# STM32.net
KiCad netlist of a schematic drawn in Altium Designer
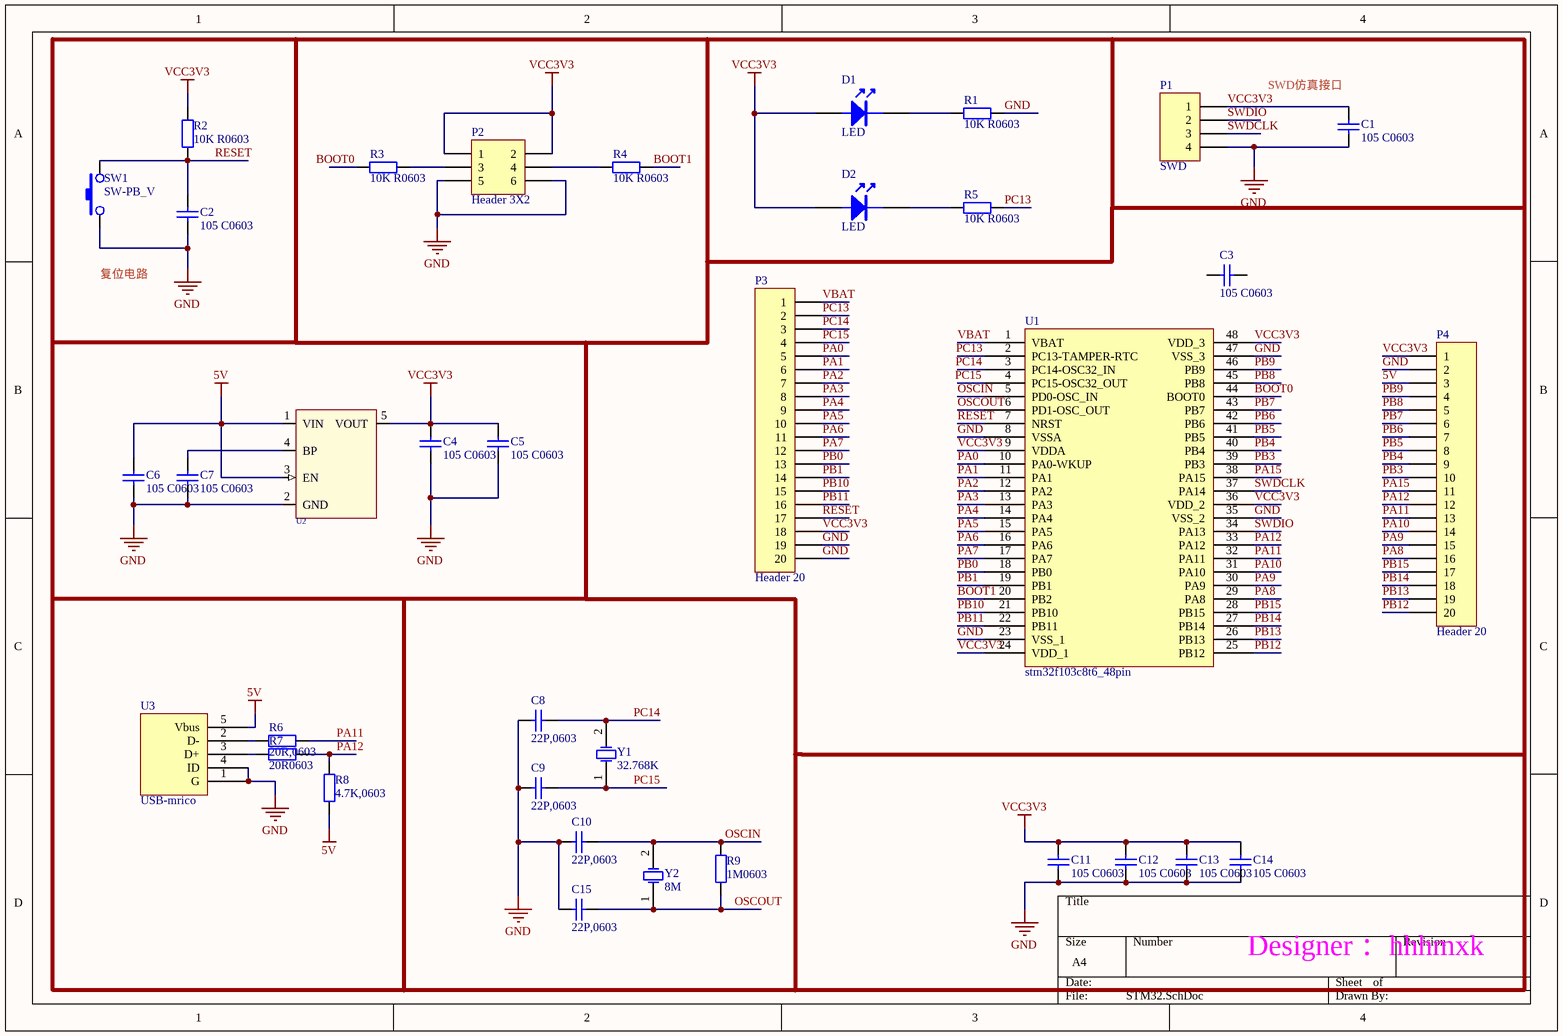
[diagram p0: STM32.SchDoc]

(export (version "E")
  (design (tool "Eeschema 10.0.6"))
  (components
    (comp (ref "C1")
      (value "105 C0603")
      (footprint "C 0603")
      (fields (field (name "PUBLISHER") "Altium Limited"))
      (libsource (lib "stm32原理图库") (part "Cap"))
    )
    (comp (ref "C2")
      (value "105 C0603")
      (footprint "C 0603")
      (fields (field (name "PUBLISHER") "Altium Limited"))
      (libsource (lib "stm32原理图库") (part "Cap"))
    )
    (comp (ref "C3")
      (value "105 C0603")
      (footprint "C 0603")
      (fields (field (name "PUBLISHER") "Altium Limited"))
      (libsource (lib "stm32原理图库") (part "Cap"))
    )
    (comp (ref "C4")
      (value "105 C0603")
      (footprint "C 0603")
      (fields (field (name "PUBLISHER") "Altium Limited"))
      (libsource (lib "stm32原理图库") (part "Cap"))
    )
    (comp (ref "C5")
      (value "105 C0603")
      (footprint "C 0603")
      (fields (field (name "PUBLISHER") "Altium Limited"))
      (libsource (lib "stm32原理图库") (part "Cap"))
    )
    (comp (ref "C6")
      (value "105 C0603")
      (footprint "C 0603")
      (fields (field (name "PUBLISHER") "Altium Limited"))
      (libsource (lib "stm32原理图库") (part "Cap"))
    )
    (comp (ref "C7")
      (value "105 C0603")
      (footprint "C 0603")
      (fields (field (name "PUBLISHER") "Altium Limited"))
      (libsource (lib "stm32原理图库") (part "Cap"))
    )
    (comp (ref "C8")
      (value "22P,0603")
      (footprint "C 0603")
      (description "Capacitor")
      (fields (field (name "PUBLISHER") "Altium Limited"))
      (libsource (lib "STM32F103C8T6") (part "Cap"))
    )
    (comp (ref "C9")
      (value "22P,0603")
      (footprint "C 0603")
      (description "Capacitor")
      (fields (field (name "PUBLISHER") "Altium Limited"))
      (libsource (lib "STM32F103C8T6") (part "Cap"))
    )
    (comp (ref "C10")
      (value "22P,0603")
      (footprint "C 0603")
      (description "Capacitor")
      (fields (field (name "PUBLISHER") "Altium Limited"))
      (libsource (lib "STM32F103C8T6") (part "Cap"))
    )
    (comp (ref "C11")
      (value "105 C0603")
      (footprint "C 0603")
      (fields (field (name "PUBLISHER") "Altium Limited"))
      (libsource (lib "stm32原理图库") (part "Cap"))
    )
    (comp (ref "C12")
      (value "105 C0603")
      (footprint "C 0603")
      (fields (field (name "PUBLISHER") "Altium Limited"))
      (libsource (lib "stm32原理图库") (part "Cap"))
    )
    (comp (ref "C13")
      (value "105 C0603")
      (footprint "C 0603")
      (fields (field (name "PUBLISHER") "Altium Limited"))
      (libsource (lib "stm32原理图库") (part "Cap"))
    )
    (comp (ref "C14")
      (value "105 C0603")
      (footprint "C 0603")
      (fields (field (name "PUBLISHER") "Altium Limited"))
      (libsource (lib "stm32原理图库") (part "Cap"))
    )
    (comp (ref "C15")
      (value "22P,0603")
      (footprint "C 0603")
      (description "Capacitor")
      (fields (field (name "PUBLISHER") "Altium Limited"))
      (libsource (lib "STM32F103C8T6") (part "Cap"))
    )
    (comp (ref "D1") (value "LED") (footprint "LED 0805G") (libsource (lib "stm32原理图库") (part "LED")))
    (comp (ref "D2") (value "LED") (footprint "LED 0805G") (libsource (lib "stm32原理图库") (part "LED")))
    (comp (ref "P1")
      (value "SWD")
      (footprint "HDR-1X4_H")
      (description "Header, 4-Pin")
      (fields (field (name "PUBLISHER") "Altium Limited"))
      (libsource (lib "stm32原理图库") (part "Header 4"))
    )
    (comp (ref "P2")
      (value "Header 3X2")
      (footprint "HDR-3X2")
      (description "Header, 3-Pin, Dual row")
      (fields (field (name "PUBLISHER") "Altium Limited"))
      (libsource (lib "stm32原理图库") (part "Header 3X2"))
    )
    (comp (ref "P3")
      (value "Header 20")
      (footprint "HDR1X20")
      (description "Header, 20-Pin")
      (fields (field (name "PUBLISHER") "Altium Limited"))
      (libsource (lib "stm32原理图库") (part "Header 20"))
    )
    (comp (ref "P4")
      (value "Header 20")
      (footprint "HDR1X20")
      (description "Header, 20-Pin")
      (fields (field (name "PUBLISHER") "Altium Limited"))
      (libsource (lib "") (part "Header 20_1"))
    )
    (comp (ref "R1")
      (value "10K R0603")
      (footprint "R 0603")
      (fields (field (name "PUBLISHER") "Altium Limited"))
      (libsource (lib "stm32原理图库") (part "Res2"))
    )
    (comp (ref "R2")
      (value "10K R0603")
      (footprint "R 0603")
      (fields (field (name "PUBLISHER") "Altium Limited"))
      (libsource (lib "") (part "Res2_1"))
    )
    (comp (ref "R3")
      (value "10K R0603")
      (footprint "R 0603")
      (fields (field (name "PUBLISHER") "Altium Limited"))
      (libsource (lib "stm32原理图库") (part "Res2"))
    )
    (comp (ref "R4")
      (value "10K R0603")
      (footprint "R 0603")
      (fields (field (name "PUBLISHER") "Altium Limited"))
      (libsource (lib "stm32原理图库") (part "Res2"))
    )
    (comp (ref "R5")
      (value "10K R0603")
      (footprint "R 0603")
      (fields (field (name "PUBLISHER") "Altium Limited"))
      (libsource (lib "stm32原理图库") (part "Res2"))
    )
    (comp (ref "R6")
      (value "20R,0603")
      (footprint "R 0603")
      (description "Resistor")
      (fields (field (name "PUBLISHER") "Altium Limited"))
      (libsource (lib "") (part "Res2_1"))
    )
    (comp (ref "R7")
      (value "20R0603")
      (footprint "R 0603")
      (description "Resistor")
      (fields (field (name "PUBLISHER") "Altium Limited"))
      (libsource (lib "") (part "Res2_1"))
    )
    (comp (ref "R8")
      (value "4.7K,0603")
      (footprint "R 0603")
      (description "Resistor")
      (fields (field (name "PUBLISHER") "Altium Limited"))
      (libsource (lib "STM32F103C8T6") (part "Res2"))
    )
    (comp (ref "R9")
      (value "1M0603")
      (footprint "R 0603")
      (description "Resistor")
      (fields (field (name "PUBLISHER") "Altium Limited"))
      (libsource (lib "STM32F103C8T6") (part "Res2"))
    )
    (comp (ref "SW1")
      (value "SW-PB_V")
      (footprint "TSW SMD-3*6*2.5")
      (libsource (lib "stm32原理图库") (part "SW-PB_V"))
    )
    (comp (ref "U1")
      (value "stm32f103c8t6_48pin")
      (footprint "TQFP48 7x7_L")
      (libsource (lib "STM32_Schlib") (part "stm32f103c8t6_48pin"))
    )
    (comp (ref "U2")
      (value "RT9193")
      (footprint "SOT23-5L")
      (fields (field (name "ICA_PARTNUM") "$$2191094$$RT9193-15CU5") (field (name "PART NUMBER") "TMP-13"))
      (libsource (lib "stm32原理图库") (part "RT9193X_5P"))
    )
    (comp (ref "U3")
      (value "USB-mrico")
      (footprint "USB-micro_B")
      (libsource (lib "STM32F103C8T6") (part "usb-STM"))
    )
    (comp (ref "Y1")
      (value "32.768K")
      (footprint "XTAL-49S DIP")
      (description "Crystal Oscillator")
      (fields (field (name "PUBLISHER") "Altium Limited"))
      (libsource (lib "STM32F103C8T6") (part "XTAL"))
    )
    (comp (ref "Y2")
      (value "8M")
      (footprint "XTAL-49S DIP")
      (description "Crystal Oscillator")
      (fields (field (name "PUBLISHER") "Altium Limited"))
      (libsource (lib "STM32F103C8T6") (part "XTAL"))
    )
  )
  (nets
    (net (code "1") (name "/BOOT0") (class "Default")
      (node (ref "R3") (pin "1") (pinfunction "1_1") (pintype "passive"))
      (node (ref "U1") (pin "44") (pinfunction "BOOT0_44") (pintype "passive"))
    )
    (net (code "2") (name "/BOOT1") (class "Default")
      (node (ref "R4") (pin "2") (pinfunction "2_2") (pintype "passive"))
      (node (ref "U1") (pin "20") (pinfunction "PB2_20") (pintype "passive"))
    )
    (net (code "3") (name "/OSCIN") (class "Default")
      (node (ref "C10") (pin "1") (pinfunction "1_1") (pintype "passive"))
      (node (ref "R9") (pin "2") (pinfunction "2_2") (pintype "passive"))
      (node (ref "U1") (pin "5") (pinfunction "PD0-OSC_IN_5") (pintype "passive"))
      (node (ref "Y2") (pin "2") (pinfunction "OSC2_2") (pintype "passive"))
    )
    (net (code "4") (name "/OSCOUT") (class "Default")
      (node (ref "C15") (pin "1") (pinfunction "1_1") (pintype "passive"))
      (node (ref "R9") (pin "1") (pinfunction "1_1") (pintype "passive"))
      (node (ref "U1") (pin "6") (pinfunction "PD1-OSC_OUT_6") (pintype "passive"))
      (node (ref "Y2") (pin "1") (pinfunction "OSC1_1") (pintype "passive"))
    )
    (net (code "5") (name "/PA0") (class "Default")
      (node (ref "P3") (pin "5") (pinfunction "5_5") (pintype "passive"))
      (node (ref "U1") (pin "10") (pinfunction "PA0-WKUP_10") (pintype "passive"))
    )
    (net (code "6") (name "/PA1") (class "Default")
      (node (ref "P3") (pin "6") (pinfunction "6_6") (pintype "passive"))
      (node (ref "U1") (pin "11") (pinfunction "PA1_11") (pintype "passive"))
    )
    (net (code "7") (name "/PA2") (class "Default")
      (node (ref "P3") (pin "7") (pinfunction "7_7") (pintype "passive"))
      (node (ref "U1") (pin "12") (pinfunction "PA2_12") (pintype "passive"))
    )
    (net (code "8") (name "/PA3") (class "Default")
      (node (ref "P3") (pin "8") (pinfunction "8_8") (pintype "passive"))
      (node (ref "U1") (pin "13") (pinfunction "PA3_13") (pintype "passive"))
    )
    (net (code "9") (name "/PA4") (class "Default")
      (node (ref "P3") (pin "9") (pinfunction "9_9") (pintype "passive"))
      (node (ref "U1") (pin "14") (pinfunction "PA4_14") (pintype "passive"))
    )
    (net (code "10") (name "/PA5") (class "Default")
      (node (ref "P3") (pin "10") (pinfunction "10_10") (pintype "passive"))
      (node (ref "U1") (pin "15") (pinfunction "PA5_15") (pintype "passive"))
    )
    (net (code "11") (name "/PA6") (class "Default")
      (node (ref "P3") (pin "11") (pinfunction "11_11") (pintype "passive"))
      (node (ref "U1") (pin "16") (pinfunction "PA6_16") (pintype "passive"))
    )
    (net (code "12") (name "/PA7") (class "Default")
      (node (ref "P3") (pin "12") (pinfunction "12_12") (pintype "passive"))
      (node (ref "U1") (pin "17") (pinfunction "PA7_17") (pintype "passive"))
    )
    (net (code "13") (name "/PA8") (class "Default")
      (node (ref "P4") (pin "16") (pinfunction "16_16") (pintype "passive"))
      (node (ref "U1") (pin "29") (pinfunction "PA8_29") (pintype "passive"))
    )
    (net (code "14") (name "/PA9") (class "Default")
      (node (ref "P4") (pin "15") (pinfunction "15_15") (pintype "passive"))
      (node (ref "U1") (pin "30") (pinfunction "PA9_30") (pintype "passive"))
    )
    (net (code "15") (name "/PA10") (class "Default")
      (node (ref "P4") (pin "14") (pinfunction "14_14") (pintype "passive"))
      (node (ref "U1") (pin "31") (pinfunction "PA10_31") (pintype "passive"))
    )
    (net (code "16") (name "/PA11") (class "Default")
      (node (ref "P4") (pin "13") (pinfunction "13_13") (pintype "passive"))
      (node (ref "R6") (pin "2") (pinfunction "2_2") (pintype "passive"))
      (node (ref "U1") (pin "32") (pinfunction "PA11_32") (pintype "passive"))
    )
    (net (code "17") (name "/PA12") (class "Default")
      (node (ref "P4") (pin "12") (pinfunction "12_12") (pintype "passive"))
      (node (ref "R7") (pin "2") (pinfunction "2_2") (pintype "passive"))
      (node (ref "R8") (pin "2") (pinfunction "2_2") (pintype "passive"))
      (node (ref "U1") (pin "33") (pinfunction "PA12_33") (pintype "passive"))
    )
    (net (code "18") (name "/PA15") (class "Default")
      (node (ref "P4") (pin "11") (pinfunction "11_11") (pintype "passive"))
      (node (ref "U1") (pin "38") (pinfunction "PA15_38") (pintype "passive"))
    )
    (net (code "19") (name "/PB0") (class "Default")
      (node (ref "P3") (pin "13") (pinfunction "13_13") (pintype "passive"))
      (node (ref "U1") (pin "18") (pinfunction "PB0_18") (pintype "passive"))
    )
    (net (code "20") (name "/PB1") (class "Default")
      (node (ref "P3") (pin "14") (pinfunction "14_14") (pintype "passive"))
      (node (ref "U1") (pin "19") (pinfunction "PB1_19") (pintype "passive"))
    )
    (net (code "21") (name "/PB3") (class "Default")
      (node (ref "P4") (pin "10") (pinfunction "10_10") (pintype "passive"))
      (node (ref "U1") (pin "39") (pinfunction "PB3_39") (pintype "passive"))
    )
    (net (code "22") (name "/PB4") (class "Default")
      (node (ref "P4") (pin "9") (pinfunction "9_9") (pintype "passive"))
      (node (ref "U1") (pin "40") (pinfunction "PB4_40") (pintype "passive"))
    )
    (net (code "23") (name "/PB5") (class "Default")
      (node (ref "P4") (pin "8") (pinfunction "8_8") (pintype "passive"))
      (node (ref "U1") (pin "41") (pinfunction "PB5_41") (pintype "passive"))
    )
    (net (code "24") (name "/PB6") (class "Default")
      (node (ref "P4") (pin "7") (pinfunction "7_7") (pintype "passive"))
      (node (ref "U1") (pin "42") (pinfunction "PB6_42") (pintype "passive"))
    )
    (net (code "25") (name "/PB7") (class "Default")
      (node (ref "P4") (pin "6") (pinfunction "6_6") (pintype "passive"))
      (node (ref "U1") (pin "43") (pinfunction "PB7_43") (pintype "passive"))
    )
    (net (code "26") (name "/PB8") (class "Default")
      (node (ref "P4") (pin "5") (pinfunction "5_5") (pintype "passive"))
      (node (ref "U1") (pin "45") (pinfunction "PB8_45") (pintype "passive"))
    )
    (net (code "27") (name "/PB9") (class "Default")
      (node (ref "P4") (pin "4") (pinfunction "4_4") (pintype "passive"))
      (node (ref "U1") (pin "46") (pinfunction "PB9_46") (pintype "passive"))
    )
    (net (code "28") (name "/PB10") (class "Default")
      (node (ref "P3") (pin "15") (pinfunction "15_15") (pintype "passive"))
      (node (ref "U1") (pin "21") (pinfunction "PB10_21") (pintype "passive"))
    )
    (net (code "29") (name "/PB11") (class "Default")
      (node (ref "P3") (pin "16") (pinfunction "16_16") (pintype "passive"))
      (node (ref "U1") (pin "22") (pinfunction "PB11_22") (pintype "passive"))
    )
    (net (code "30") (name "/PB12") (class "Default")
      (node (ref "P4") (pin "20") (pinfunction "20_20") (pintype "passive"))
      (node (ref "U1") (pin "25") (pinfunction "PB12_25") (pintype "passive"))
    )
    (net (code "31") (name "/PB13") (class "Default")
      (node (ref "P4") (pin "19") (pinfunction "19_19") (pintype "passive"))
      (node (ref "U1") (pin "26") (pinfunction "PB13_26") (pintype "passive"))
    )
    (net (code "32") (name "/PB14") (class "Default")
      (node (ref "P4") (pin "18") (pinfunction "18_18") (pintype "passive"))
      (node (ref "U1") (pin "27") (pinfunction "PB14_27") (pintype "passive"))
    )
    (net (code "33") (name "/PB15") (class "Default")
      (node (ref "P4") (pin "17") (pinfunction "17_17") (pintype "passive"))
      (node (ref "U1") (pin "28") (pinfunction "PB15_28") (pintype "passive"))
    )
    (net (code "34") (name "/PC13") (class "Default")
      (node (ref "P3") (pin "2") (pinfunction "2_2") (pintype "passive"))
      (node (ref "R5") (pin "2") (pinfunction "2_2") (pintype "passive"))
      (node (ref "U1") (pin "2") (pinfunction "PC13-TAMPER-RTC_2") (pintype "passive"))
    )
    (net (code "35") (name "/PC14") (class "Default")
      (node (ref "C8") (pin "1") (pinfunction "1_1") (pintype "passive"))
      (node (ref "P3") (pin "3") (pinfunction "3_3") (pintype "passive"))
      (node (ref "U1") (pin "3") (pinfunction "PC14-OSC32_IN_3") (pintype "passive"))
      (node (ref "Y1") (pin "2") (pinfunction "OSC2_2") (pintype "passive"))
    )
    (net (code "36") (name "/PC15") (class "Default")
      (node (ref "C9") (pin "1") (pinfunction "1_1") (pintype "passive"))
      (node (ref "P3") (pin "4") (pinfunction "4_4") (pintype "passive"))
      (node (ref "U1") (pin "4") (pinfunction "PC15-OSC32_OUT_4") (pintype "passive"))
      (node (ref "Y1") (pin "1") (pinfunction "OSC1_1") (pintype "passive"))
    )
    (net (code "37") (name "/RESET") (class "Default")
      (node (ref "C2") (pin "2") (pinfunction "2_2") (pintype "passive"))
      (node (ref "P3") (pin "17") (pinfunction "17_17") (pintype "passive"))
      (node (ref "R2") (pin "1") (pinfunction "1_1") (pintype "passive"))
      (node (ref "SW1") (pin "2") (pinfunction "2_2") (pintype "passive"))
      (node (ref "U1") (pin "7") (pinfunction "NRST_7") (pintype "passive"))
    )
    (net (code "38") (name "/SWDCLK") (class "Default")
      (node (ref "P1") (pin "3") (pinfunction "3_3") (pintype "passive"))
      (node (ref "U1") (pin "37") (pinfunction "PA14_37") (pintype "passive"))
    )
    (net (code "39") (name "/SWDIO") (class "Default")
      (node (ref "P1") (pin "2") (pinfunction "2_2") (pintype "passive"))
      (node (ref "U1") (pin "34") (pinfunction "PA13_34") (pintype "passive"))
    )
    (net (code "40") (name "/VBAT") (class "Default")
      (node (ref "P3") (pin "1") (pinfunction "1_1") (pintype "passive"))
      (node (ref "U1") (pin "1") (pinfunction "VBAT_1") (pintype "passive"))
    )
    (net (code "41") (name "5V") (class "Default")
      (node (ref "C6") (pin "2") (pinfunction "2_2") (pintype "passive"))
      (node (ref "P4") (pin "3") (pinfunction "3_3") (pintype "passive"))
      (node (ref "R8") (pin "1") (pinfunction "1_1") (pintype "passive"))
      (node (ref "U2") (pin "1") (pinfunction "VIN_1") (pintype "power_in"))
      (node (ref "U2") (pin "3") (pinfunction "EN_3") (pintype "input"))
      (node (ref "U3") (pin "5") (pinfunction "Vbus_5") (pintype "passive"))
    )
    (net (code "42") (name "GND") (class "Default")
      (node (ref "C1") (pin "1") (pinfunction "1_1") (pintype "passive"))
      (node (ref "C10") (pin "2") (pinfunction "2_2") (pintype "passive"))
      (node (ref "C11") (pin "1") (pinfunction "1_1") (pintype "passive"))
      (node (ref "C12") (pin "1") (pinfunction "1_1") (pintype "passive"))
      (node (ref "C13") (pin "1") (pinfunction "1_1") (pintype "passive"))
      (node (ref "C14") (pin "1") (pinfunction "1_1") (pintype "passive"))
      (node (ref "C15") (pin "2") (pinfunction "2_2") (pintype "passive"))
      (node (ref "C2") (pin "1") (pinfunction "1_1") (pintype "passive"))
      (node (ref "C4") (pin "1") (pinfunction "1_1") (pintype "passive"))
      (node (ref "C5") (pin "1") (pinfunction "1_1") (pintype "passive"))
      (node (ref "C6") (pin "1") (pinfunction "1_1") (pintype "passive"))
      (node (ref "C7") (pin "1") (pinfunction "1_1") (pintype "passive"))
      (node (ref "C8") (pin "2") (pinfunction "2_2") (pintype "passive"))
      (node (ref "C9") (pin "2") (pinfunction "2_2") (pintype "passive"))
      (node (ref "P1") (pin "4") (pinfunction "4_4") (pintype "passive"))
      (node (ref "P2") (pin "5") (pinfunction "5_5") (pintype "passive"))
      (node (ref "P2") (pin "6") (pinfunction "6_6") (pintype "passive"))
      (node (ref "P3") (pin "19") (pinfunction "19_19") (pintype "passive"))
      (node (ref "P3") (pin "20") (pinfunction "20_20") (pintype "passive"))
      (node (ref "P4") (pin "2") (pinfunction "2_2") (pintype "passive"))
      (node (ref "R1") (pin "2") (pinfunction "2_2") (pintype "passive"))
      (node (ref "SW1") (pin "1") (pinfunction "1_1") (pintype "passive"))
      (node (ref "U1") (pin "23") (pinfunction "VSS_1_23") (pintype "passive"))
      (node (ref "U1") (pin "35") (pinfunction "VSS_2_35") (pintype "passive"))
      (node (ref "U1") (pin "47") (pinfunction "VSS_3_47") (pintype "passive"))
      (node (ref "U1") (pin "8") (pinfunction "VSSA_8") (pintype "passive"))
      (node (ref "U2") (pin "2") (pinfunction "GND_2") (pintype "power_in"))
      (node (ref "U3") (pin "1") (pinfunction "G_1") (pintype "passive"))
      (node (ref "U3") (pin "4") (pinfunction "ID_4") (pintype "passive"))
    )
    (net (code "43") (name "Net-(D1-Pad2)") (class "Default")
      (node (ref "D1") (pin "2") (pinfunction "2_2") (pintype "passive"))
      (node (ref "R1") (pin "1") (pinfunction "1_1") (pintype "passive"))
    )
    (net (code "44") (name "Net-(D2-Pad2)") (class "Default")
      (node (ref "D2") (pin "2") (pinfunction "2_2") (pintype "passive"))
      (node (ref "R5") (pin "1") (pinfunction "1_1") (pintype "passive"))
    )
    (net (code "45") (name "Net-(P2-Pad3)") (class "Default")
      (node (ref "P2") (pin "3") (pinfunction "3_3") (pintype "passive"))
      (node (ref "R3") (pin "2") (pinfunction "2_2") (pintype "passive"))
    )
    (net (code "46") (name "Net-(P2-Pad4)") (class "Default")
      (node (ref "P2") (pin "4") (pinfunction "4_4") (pintype "passive"))
      (node (ref "R4") (pin "1") (pinfunction "1_1") (pintype "passive"))
    )
    (net (code "47") (name "Net-(U2-BP)") (class "Default")
      (node (ref "C7") (pin "2") (pinfunction "2_2") (pintype "passive"))
      (node (ref "U2") (pin "4") (pinfunction "BP_4") (pintype "passive"))
    )
    (net (code "48") (name "Net-(U3-D+)") (class "Default")
      (node (ref "R7") (pin "1") (pinfunction "1_1") (pintype "passive"))
      (node (ref "U3") (pin "3") (pinfunction "D+_3") (pintype "passive"))
    )
    (net (code "49") (name "Net-(U3-D-)") (class "Default")
      (node (ref "R6") (pin "1") (pinfunction "1_1") (pintype "passive"))
      (node (ref "U3") (pin "2") (pinfunction "D-_2") (pintype "passive"))
    )
    (net (code "50") (name "VCC3V3") (class "Default")
      (node (ref "C1") (pin "2") (pinfunction "2_2") (pintype "passive"))
      (node (ref "C11") (pin "2") (pinfunction "2_2") (pintype "passive"))
      (node (ref "C12") (pin "2") (pinfunction "2_2") (pintype "passive"))
      (node (ref "C13") (pin "2") (pinfunction "2_2") (pintype "passive"))
      (node (ref "C14") (pin "2") (pinfunction "2_2") (pintype "passive"))
      (node (ref "C4") (pin "2") (pinfunction "2_2") (pintype "passive"))
      (node (ref "C5") (pin "2") (pinfunction "2_2") (pintype "passive"))
      (node (ref "D1") (pin "1") (pinfunction "1_1") (pintype "passive"))
      (node (ref "D2") (pin "1") (pinfunction "1_1") (pintype "passive"))
      (node (ref "P1") (pin "1") (pinfunction "1_1") (pintype "passive"))
      (node (ref "P2") (pin "1") (pinfunction "1_1") (pintype "passive"))
      (node (ref "P2") (pin "2") (pinfunction "2_2") (pintype "passive"))
      (node (ref "P3") (pin "18") (pinfunction "18_18") (pintype "passive"))
      (node (ref "P4") (pin "1") (pinfunction "1_1") (pintype "passive"))
      (node (ref "R2") (pin "2") (pinfunction "2_2") (pintype "passive"))
      (node (ref "U1") (pin "24") (pinfunction "VDD_1_24") (pintype "passive"))
      (node (ref "U1") (pin "36") (pinfunction "VDD_2_36") (pintype "passive"))
      (node (ref "U1") (pin "48") (pinfunction "VDD_3_48") (pintype "passive"))
      (node (ref "U1") (pin "9") (pinfunction "VDDA_9") (pintype "passive"))
      (node (ref "U2") (pin "5") (pinfunction "VOUT_5") (pintype "power_in"))
    )
    (net (code "51") (name "unconnected-(C3-Pad1)") (class "Default")
      (node (ref "C3") (pin "1") (pinfunction "1_1") (pintype "passive"))
    )
    (net (code "52") (name "unconnected-(C3-Pad2)") (class "Default")
      (node (ref "C3") (pin "2") (pinfunction "2_2") (pintype "passive"))
    )
  )
)
